# MJ818_clone_-_all_driver.net
KiCad netlist of a schematic drawn in EAGLE
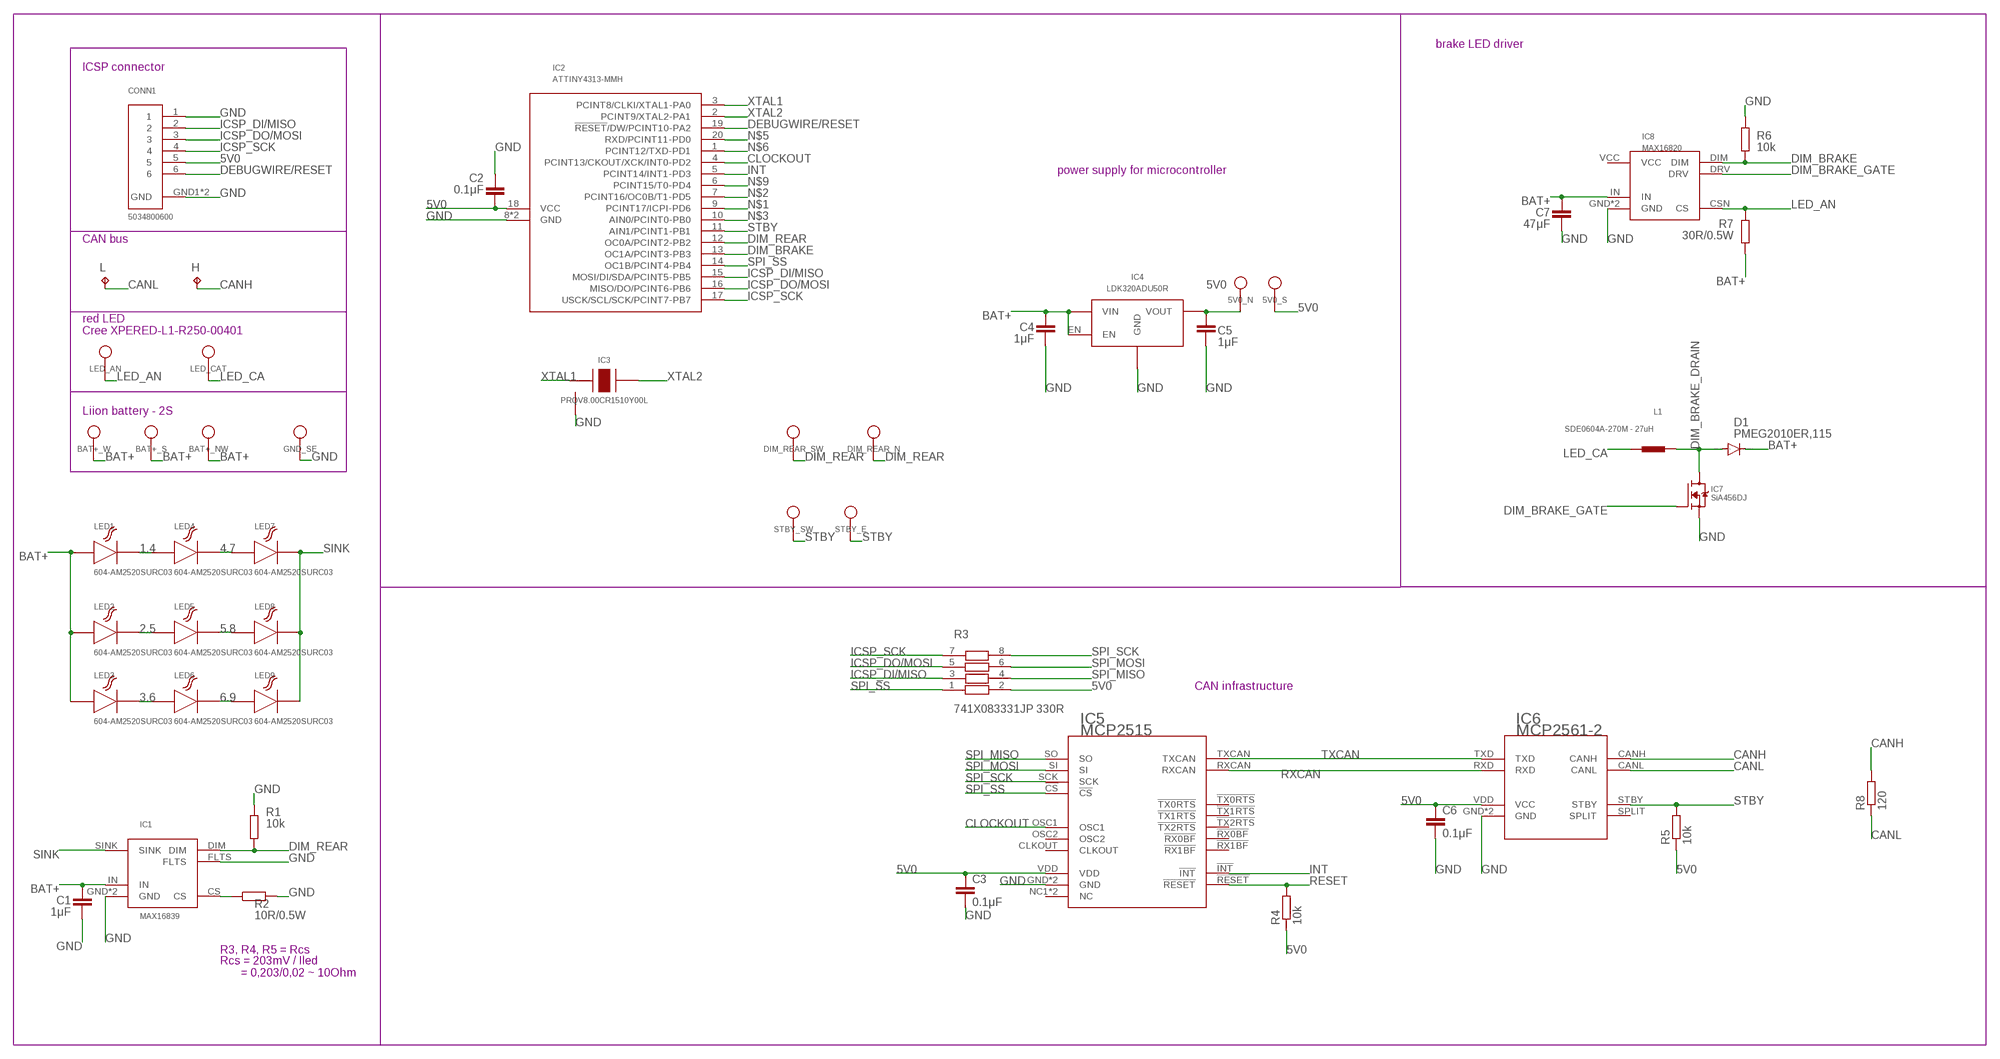
[diagram p0: schematic, sheet 1]

(export (version "E")
  (design (tool "Eeschema 10.0.6"))
  (components
    (comp (ref "5V0_N")
      (value "TPTH")
      (footprint "eagle-import:TH")
      (libsource (lib "eagle-import") (part "TPTH"))
    )
    (comp (ref "5V0_S")
      (value "TPTH")
      (footprint "eagle-import:TH")
      (libsource (lib "eagle-import") (part "TPTH"))
    )
    (comp (ref "BAT+_NW")
      (value "TPTH")
      (footprint "eagle-import:TH")
      (libsource (lib "eagle-import") (part "TPTH"))
    )
    (comp (ref "BAT+_S")
      (value "TPSMT")
      (footprint "eagle-import:SMT")
      (libsource (lib "eagle-import") (part "TPSMT"))
    )
    (comp (ref "BAT+_W")
      (value "TPTH")
      (footprint "eagle-import:TH")
      (libsource (lib "eagle-import") (part "TPTH"))
    )
    (comp (ref "C1")
      (value "1μF")
      (footprint "eagle-import:C0402")
      (libsource (lib "eagle-import") (part "C-EUC0402"))
    )
    (comp (ref "C2")
      (value "0.1μF")
      (footprint "eagle-import:C0402")
      (libsource (lib "eagle-import") (part "C-EUC0402"))
    )
    (comp (ref "C3")
      (value "0.1μF")
      (footprint "eagle-import:C1206")
      (libsource (lib "eagle-import") (part "C-EUC1206"))
    )
    (comp (ref "C4")
      (value "1μF")
      (footprint "eagle-import:C0402")
      (libsource (lib "eagle-import") (part "C-EUC0402"))
    )
    (comp (ref "C5")
      (value "1μF")
      (footprint "eagle-import:C0402")
      (libsource (lib "eagle-import") (part "C-EUC0402"))
    )
    (comp (ref "C6")
      (value "0.1μF")
      (footprint "eagle-import:C1206")
      (libsource (lib "eagle-import") (part "C-EUC1206"))
    )
    (comp (ref "C7")
      (value "47μF")
      (footprint "eagle-import:C1206")
      (libsource (lib "eagle-import") (part "C-EUC1206"))
    )
    (comp (ref "CONN1")
      (value "5034800600")
      (footprint "eagle-import:SMT")
      (libsource (lib "eagle-import") (part "5034800600"))
    )
    (comp (ref "D1")
      (value "PMEG2010ER,115")
      (footprint "eagle-import:SOD123")
      (libsource (lib "eagle-import") (part "DIODE-SOD123"))
    )
    (comp (ref "DIM_REAR_N")
      (value "TPTH")
      (footprint "eagle-import:TH")
      (libsource (lib "eagle-import") (part "TPTH"))
    )
    (comp (ref "DIM_REAR_SW")
      (value "TPTH")
      (footprint "eagle-import:TH")
      (libsource (lib "eagle-import") (part "TPTH"))
    )
    (comp (ref "GND_SE")
      (value "TPTH")
      (footprint "eagle-import:TH")
      (libsource (lib "eagle-import") (part "TPTH"))
    )
    (comp (ref "H")
      (value "TPB2,54")
      (footprint "eagle-import:B2,54")
      (libsource (lib "eagle-import") (part "TPB2,54"))
    )
    (comp (ref "IC1")
      (value "MAX16839")
      (footprint "eagle-import:TDFN-6-EP")
      (libsource (lib "eagle-import") (part "MAX16839"))
    )
    (comp (ref "IC2")
      (value "ATTINY4313-MMH")
      (footprint "eagle-import:VQFN-20")
      (fields (field (name "SPICEPREFIX") "X"))
      (libsource (lib "eagle-import") (part "ATTINY4313VQFN-20"))
    )
    (comp (ref "IC3")
      (value "PRQV8.00CR1510Y00L")
      (footprint "eagle-import:SMT")
      (libsource (lib "eagle-import") (part "PRQV"))
    )
    (comp (ref "IC4")
      (value "LDK320ADU50R")
      (footprint "eagle-import:SOT-23-5L")
      (libsource (lib "eagle-import") (part "LDK320SOT-23-5L"))
    )
    (comp (ref "IC5")
      (value "MCP2515")
      (footprint "eagle-import:QFN20")
      (libsource (lib "eagle-import") (part "MCP2515-I-ML"))
    )
    (comp (ref "IC6")
      (value "MCP2561-2")
      (footprint "eagle-import:DFN10")
      (libsource (lib "eagle-import") (part "MCP2561-2"))
    )
    (comp (ref "IC7")
      (value "SiA456DJ")
      (footprint "eagle-import:SC-70-6")
      (libsource (lib "eagle-import") (part "SIA456DJ"))
    )
    (comp (ref "IC8")
      (value "MAX16820")
      (footprint "eagle-import:TDFN-6-EP")
      (libsource (lib "eagle-import") (part "MAX16820"))
    )
    (comp (ref "L")
      (value "TPB2,54")
      (footprint "eagle-import:B2,54")
      (libsource (lib "eagle-import") (part "TPB2,54"))
    )
    (comp (ref "L1")
      (value "SDE0604A-270M - 27uH")
      (footprint "eagle-import:SMT")
      (libsource (lib "eagle-import") (part "DE0604A-778075"))
    )
    (comp (ref "LED1")
      (value "604-AM2520SURC03")
      (footprint "eagle-import:SMD")
      (libsource (lib "eagle-import") (part "AM2520SURC03-31454"))
    )
    (comp (ref "LED2")
      (value "604-AM2520SURC03")
      (footprint "eagle-import:SMD")
      (libsource (lib "eagle-import") (part "AM2520SURC03-31454"))
    )
    (comp (ref "LED3")
      (value "604-AM2520SURC03")
      (footprint "eagle-import:SMD")
      (libsource (lib "eagle-import") (part "AM2520SURC03-31454"))
    )
    (comp (ref "LED4")
      (value "604-AM2520SURC03")
      (footprint "eagle-import:SMD")
      (libsource (lib "eagle-import") (part "AM2520SURC03-31454"))
    )
    (comp (ref "LED5")
      (value "604-AM2520SURC03")
      (footprint "eagle-import:SMD")
      (libsource (lib "eagle-import") (part "AM2520SURC03-31454"))
    )
    (comp (ref "LED6")
      (value "604-AM2520SURC03")
      (footprint "eagle-import:SMD")
      (libsource (lib "eagle-import") (part "AM2520SURC03-31454"))
    )
    (comp (ref "LED7")
      (value "604-AM2520SURC03")
      (footprint "eagle-import:SMD")
      (libsource (lib "eagle-import") (part "AM2520SURC03-31454"))
    )
    (comp (ref "LED8")
      (value "604-AM2520SURC03")
      (footprint "eagle-import:SMD")
      (libsource (lib "eagle-import") (part "AM2520SURC03-31454"))
    )
    (comp (ref "LED9")
      (value "604-AM2520SURC03")
      (footprint "eagle-import:SMD")
      (libsource (lib "eagle-import") (part "AM2520SURC03-31454"))
    )
    (comp (ref "LED_AN")
      (value "TPTH")
      (footprint "eagle-import:TH")
      (libsource (lib "eagle-import") (part "TPTH"))
    )
    (comp (ref "LED_CAT")
      (value "TPTH")
      (footprint "eagle-import:TH")
      (libsource (lib "eagle-import") (part "TPTH"))
    )
    (comp (ref "R1")
      (value "10k")
      (footprint "eagle-import:R0402")
      (libsource (lib "eagle-import") (part "R-EU_R0402"))
    )
    (comp (ref "R2")
      (value "10R/0.5W")
      (footprint "eagle-import:R0603")
      (libsource (lib "eagle-import") (part "R-EU_R0603"))
    )
    (comp (ref "R3")
      (value "741X083331JP 330R")
      (footprint "eagle-import:0402")
      (libsource (lib "eagle-import") (part "741X083331JP"))
    )
    (comp (ref "R4")
      (value "10k")
      (footprint "eagle-import:R0402")
      (libsource (lib "eagle-import") (part "R-EU_R0402"))
    )
    (comp (ref "R5")
      (value "10k")
      (footprint "eagle-import:R0603")
      (libsource (lib "eagle-import") (part "R-EU_R0603"))
    )
    (comp (ref "R6")
      (value "10k")
      (footprint "eagle-import:R0402")
      (libsource (lib "eagle-import") (part "R-EU_R0402"))
    )
    (comp (ref "R7")
      (value "30R/0.5W")
      (footprint "eagle-import:R1206")
      (libsource (lib "eagle-import") (part "R-EU_R1206"))
    )
    (comp (ref "R8")
      (value "120")
      (footprint "eagle-import:R0805")
      (libsource (lib "eagle-import") (part "R-EU_R0805"))
    )
    (comp (ref "STBY_E")
      (value "TPTH")
      (footprint "eagle-import:TH")
      (libsource (lib "eagle-import") (part "TPTH"))
    )
    (comp (ref "STBY_SW")
      (value "TPTH")
      (footprint "eagle-import:TH")
      (libsource (lib "eagle-import") (part "TPTH"))
    )
  )
  (nets
    (net (code "1") (name "/1.4") (class "Default")
      (node (ref "LED1") (pin "C") (pinfunction "C_C") (pintype "bidirectional"))
      (node (ref "LED4") (pin "A") (pinfunction "A_A") (pintype "bidirectional"))
    )
    (net (code "2") (name "/2.5") (class "Default")
      (node (ref "LED2") (pin "C") (pinfunction "C_C") (pintype "bidirectional"))
      (node (ref "LED5") (pin "A") (pinfunction "A_A") (pintype "bidirectional"))
    )
    (net (code "3") (name "/3.6") (class "Default")
      (node (ref "LED3") (pin "C") (pinfunction "C_C") (pintype "bidirectional"))
      (node (ref "LED6") (pin "A") (pinfunction "A_A") (pintype "bidirectional"))
    )
    (net (code "4") (name "/4.7") (class "Default")
      (node (ref "LED4") (pin "C") (pinfunction "C_C") (pintype "bidirectional"))
      (node (ref "LED7") (pin "A") (pinfunction "A_A") (pintype "bidirectional"))
    )
    (net (code "5") (name "/5.8") (class "Default")
      (node (ref "LED5") (pin "C") (pinfunction "C_C") (pintype "bidirectional"))
      (node (ref "LED8") (pin "A") (pinfunction "A_A") (pintype "bidirectional"))
    )
    (net (code "6") (name "/5V0") (class "Default")
      (node (ref "5V0_N") (pin "TP$1") (pinfunction "TP$1_TP$1") (pintype "bidirectional"))
      (node (ref "5V0_S") (pin "TP$1") (pinfunction "TP$1_TP$1") (pintype "bidirectional"))
      (node (ref "C2") (pin "1") (pinfunction "1_1") (pintype "passive"))
      (node (ref "C3") (pin "1") (pinfunction "1_1") (pintype "passive"))
      (node (ref "C5") (pin "2") (pinfunction "2_2") (pintype "passive"))
      (node (ref "C6") (pin "1") (pinfunction "1_1") (pintype "passive"))
      (node (ref "CONN1") (pin "5") (pinfunction "5_5") (pintype "bidirectional"))
      (node (ref "IC2") (pin "18") (pinfunction "VCC_18") (pintype "bidirectional"))
      (node (ref "IC4") (pin "OUT") (pinfunction "VOUT_OUT") (pintype "bidirectional"))
      (node (ref "IC5") (pin "VDD") (pinfunction "VDD_VDD") (pintype "power_in"))
      (node (ref "IC6") (pin "VDD") (pinfunction "VCC_VDD") (pintype "power_in"))
      (node (ref "R3") (pin "2") (pinfunction "2_2") (pintype "bidirectional"))
      (node (ref "R4") (pin "1") (pinfunction "1_1") (pintype "passive"))
      (node (ref "R5") (pin "1") (pinfunction "1_1") (pintype "passive"))
    )
    (net (code "7") (name "/6.9") (class "Default")
      (node (ref "LED6") (pin "C") (pinfunction "C_C") (pintype "bidirectional"))
      (node (ref "LED9") (pin "A") (pinfunction "A_A") (pintype "bidirectional"))
    )
    (net (code "8") (name "/BAT+") (class "Default")
      (node (ref "BAT+_NW") (pin "TP$1") (pinfunction "TP$1_TP$1") (pintype "bidirectional"))
      (node (ref "BAT+_S") (pin "P$1") (pinfunction "TP$1_P$1") (pintype "bidirectional"))
      (node (ref "BAT+_W") (pin "TP$1") (pinfunction "TP$1_TP$1") (pintype "bidirectional"))
      (node (ref "C1") (pin "2") (pinfunction "2_2") (pintype "passive"))
      (node (ref "C4") (pin "1") (pinfunction "1_1") (pintype "passive"))
      (node (ref "C7") (pin "1") (pinfunction "1_1") (pintype "passive"))
      (node (ref "D1") (pin "C") (pinfunction "C_C") (pintype "passive"))
      (node (ref "IC1") (pin "IN") (pinfunction "IN_IN") (pintype "power_in"))
      (node (ref "IC4") (pin "EN") (pinfunction "EN_EN") (pintype "bidirectional"))
      (node (ref "IC4") (pin "IN") (pinfunction "VIN_IN") (pintype "bidirectional"))
      (node (ref "IC8") (pin "IN") (pinfunction "IN_IN") (pintype "power_in"))
      (node (ref "LED1") (pin "A") (pinfunction "A_A") (pintype "bidirectional"))
      (node (ref "LED2") (pin "A") (pinfunction "A_A") (pintype "bidirectional"))
      (node (ref "LED3") (pin "A") (pinfunction "A_A") (pintype "bidirectional"))
      (node (ref "R7") (pin "2") (pinfunction "2_2") (pintype "passive"))
    )
    (net (code "9") (name "/CANH") (class "Default")
      (node (ref "H") (pin "TP") (pinfunction "TP_TP") (pintype "input"))
      (node (ref "IC6") (pin "CANH") (pinfunction "CANH_CANH") (pintype "bidirectional"))
      (node (ref "R8") (pin "2") (pinfunction "2_2") (pintype "passive"))
    )
    (net (code "10") (name "/CANL") (class "Default")
      (node (ref "IC6") (pin "CANL") (pinfunction "CANL_CANL") (pintype "bidirectional"))
      (node (ref "L") (pin "TP") (pinfunction "TP_TP") (pintype "input"))
      (node (ref "R8") (pin "1") (pinfunction "1_1") (pintype "passive"))
    )
    (net (code "11") (name "/CLOCKOUT") (class "Default")
      (node (ref "IC2") (pin "4") (pinfunction "PCINT13/CKOUT/XCK/INT0-PD2_4") (pintype "bidirectional"))
      (node (ref "IC5") (pin "OSC1") (pinfunction "OSC1_OSC1") (pintype "bidirectional"))
    )
    (net (code "12") (name "/DEBUGWIRE{slash}RESET") (class "Default")
      (node (ref "CONN1") (pin "6") (pinfunction "6_6") (pintype "bidirectional"))
      (node (ref "IC2") (pin "19") (pinfunction "~{RESET}/DW/PCINT10-PA2_19") (pintype "bidirectional"))
    )
    (net (code "13") (name "/DIM_BRAKE") (class "Default")
      (node (ref "IC2") (pin "13") (pinfunction "OC1A/PCINT3-PB3_13") (pintype "bidirectional"))
      (node (ref "IC8") (pin "DIM") (pinfunction "DIM_DIM") (pintype "bidirectional"))
      (node (ref "R6") (pin "1") (pinfunction "1_1") (pintype "passive"))
    )
    (net (code "14") (name "/DIM_BRAKE_DRAIN") (class "Default")
      (node (ref "D1") (pin "A") (pinfunction "A_A") (pintype "passive"))
      (node (ref "IC7") (pin "1D") (pinfunction "D_1D") (pintype "passive"))
      (node (ref "IC7") (pin "2D") (pinfunction "D_2D") (pintype "passive"))
      (node (ref "IC7") (pin "5D") (pinfunction "D_5D") (pintype "passive"))
      (node (ref "IC7") (pin "6D") (pinfunction "D_6D") (pintype "passive"))
      (node (ref "IC7") (pin "D") (pinfunction "D_D") (pintype "passive"))
      (node (ref "L1") (pin "P$2") (pinfunction "P$2_P$2") (pintype "bidirectional"))
    )
    (net (code "15") (name "/DIM_BRAKE_GATE") (class "Default")
      (node (ref "IC7") (pin "3G") (pinfunction "G_3G") (pintype "passive"))
      (node (ref "IC8") (pin "DRV") (pinfunction "DRV_DRV") (pintype "bidirectional"))
    )
    (net (code "16") (name "/DIM_REAR") (class "Default")
      (node (ref "DIM_REAR_N") (pin "TP$1") (pinfunction "TP$1_TP$1") (pintype "bidirectional"))
      (node (ref "DIM_REAR_SW") (pin "TP$1") (pinfunction "TP$1_TP$1") (pintype "bidirectional"))
      (node (ref "IC1") (pin "DIM") (pinfunction "DIM_DIM") (pintype "bidirectional"))
      (node (ref "IC2") (pin "12") (pinfunction "OC0A/PCINT2-PB2_12") (pintype "bidirectional"))
      (node (ref "R1") (pin "1") (pinfunction "1_1") (pintype "passive"))
    )
    (net (code "17") (name "/GND") (class "Default")
      (node (ref "C1") (pin "1") (pinfunction "1_1") (pintype "passive"))
      (node (ref "C2") (pin "2") (pinfunction "2_2") (pintype "passive"))
      (node (ref "C3") (pin "2") (pinfunction "2_2") (pintype "passive"))
      (node (ref "C4") (pin "2") (pinfunction "2_2") (pintype "passive"))
      (node (ref "C5") (pin "1") (pinfunction "1_1") (pintype "passive"))
      (node (ref "C6") (pin "2") (pinfunction "2_2") (pintype "passive"))
      (node (ref "C7") (pin "2") (pinfunction "2_2") (pintype "passive"))
      (node (ref "CONN1") (pin "1") (pinfunction "1_1") (pintype "bidirectional"))
      (node (ref "CONN1") (pin "GND1") (pinfunction "GND_GND1") (pintype "bidirectional"))
      (node (ref "CONN1") (pin "GND2") (pinfunction "GND_GND2") (pintype "bidirectional"))
      (node (ref "GND_SE") (pin "TP$1") (pinfunction "TP$1_TP$1") (pintype "bidirectional"))
      (node (ref "IC1") (pin "FLTS") (pinfunction "FLTS_FLTS") (pintype "bidirectional"))
      (node (ref "IC1") (pin "GND") (pinfunction "GND_GND") (pintype "power_in"))
      (node (ref "IC1") (pin "GND1") (pinfunction "GND_GND1") (pintype "power_in"))
      (node (ref "IC2") (pin "8") (pinfunction "GND_8") (pintype "bidirectional"))
      (node (ref "IC2") (pin "GND") (pinfunction "GND_GND") (pintype "bidirectional"))
      (node (ref "IC3") (pin "GND") (pinfunction "GND_GND") (pintype "bidirectional"))
      (node (ref "IC4") (pin "GND") (pinfunction "GND_GND") (pintype "bidirectional"))
      (node (ref "IC5") (pin "GND") (pinfunction "GND_GND") (pintype "power_in"))
      (node (ref "IC5") (pin "GND6") (pinfunction "GND_GND6") (pintype "power_in"))
      (node (ref "IC6") (pin "GND") (pinfunction "GND_GND") (pintype "power_in"))
      (node (ref "IC6") (pin "VSS") (pinfunction "GND_VSS") (pintype "power_in"))
      (node (ref "IC7") (pin "4S") (pinfunction "S_4S") (pintype "passive"))
      (node (ref "IC7") (pin "S") (pinfunction "S_S") (pintype "passive"))
      (node (ref "IC8") (pin "GND") (pinfunction "GND_GND") (pintype "power_in"))
      (node (ref "IC8") (pin "GND1") (pinfunction "GND_GND1") (pintype "power_in"))
      (node (ref "R1") (pin "2") (pinfunction "2_2") (pintype "passive"))
      (node (ref "R2") (pin "2") (pinfunction "2_2") (pintype "passive"))
      (node (ref "R6") (pin "2") (pinfunction "2_2") (pintype "passive"))
    )
    (net (code "18") (name "/ICSP_DI{slash}MISO") (class "Default")
      (node (ref "CONN1") (pin "2") (pinfunction "2_2") (pintype "bidirectional"))
      (node (ref "IC2") (pin "15") (pinfunction "MOSI/DI/SDA/PCINT5-PB5_15") (pintype "bidirectional"))
      (node (ref "R3") (pin "3") (pinfunction "3_3") (pintype "bidirectional"))
    )
    (net (code "19") (name "/ICSP_DO{slash}MOSI") (class "Default")
      (node (ref "CONN1") (pin "3") (pinfunction "3_3") (pintype "bidirectional"))
      (node (ref "IC2") (pin "16") (pinfunction "MISO/DO/PCINT6-PB6_16") (pintype "bidirectional"))
      (node (ref "R3") (pin "5") (pinfunction "5_5") (pintype "bidirectional"))
    )
    (net (code "20") (name "/ICSP_SCK") (class "Default")
      (node (ref "CONN1") (pin "4") (pinfunction "4_4") (pintype "bidirectional"))
      (node (ref "IC2") (pin "17") (pinfunction "USCK/SCL/SCK/PCINT7-PB7_17") (pintype "bidirectional"))
      (node (ref "R3") (pin "7") (pinfunction "7_7") (pintype "bidirectional"))
    )
    (net (code "21") (name "/INT") (class "Default")
      (node (ref "IC2") (pin "5") (pinfunction "PCINT14/INT1-PD3_5") (pintype "bidirectional"))
      (node (ref "IC5") (pin "!INT!") (pinfunction "~{INT}_!INT!") (pintype "bidirectional"))
    )
    (net (code "22") (name "/LED_AN") (class "Default")
      (node (ref "IC8") (pin "CSN") (pinfunction "CS_CSN") (pintype "bidirectional"))
      (node (ref "LED_AN") (pin "TP$1") (pinfunction "TP$1_TP$1") (pintype "bidirectional"))
      (node (ref "R7") (pin "1") (pinfunction "1_1") (pintype "passive"))
    )
    (net (code "23") (name "/LED_CA") (class "Default")
      (node (ref "L1") (pin "P$1") (pinfunction "P$1_P$1") (pintype "bidirectional"))
      (node (ref "LED_CAT") (pin "TP$1") (pinfunction "TP$1_TP$1") (pintype "bidirectional"))
    )
    (net (code "24") (name "/N$1") (class "Default")
      (node (ref "IC2") (pin "9") (pinfunction "PCINT17/ICPI-PD6_9") (pintype "bidirectional"))
    )
    (net (code "25") (name "/N$2") (class "Default")
      (node (ref "IC2") (pin "7") (pinfunction "PCINT16/OC0B/T1-PD5_7") (pintype "bidirectional"))
    )
    (net (code "26") (name "/N$3") (class "Default")
      (node (ref "IC2") (pin "10") (pinfunction "AIN0/PCINT0-PB0_10") (pintype "bidirectional"))
    )
    (net (code "27") (name "/N$5") (class "Default")
      (node (ref "IC2") (pin "20") (pinfunction "RXD/PCINT11-PD0_20") (pintype "bidirectional"))
    )
    (net (code "28") (name "/N$6") (class "Default")
      (node (ref "IC2") (pin "1") (pinfunction "PCINT12/TXD-PD1_1") (pintype "bidirectional"))
    )
    (net (code "29") (name "/N$9") (class "Default")
      (node (ref "IC2") (pin "6") (pinfunction "PCINT15/T0-PD4_6") (pintype "bidirectional"))
    )
    (net (code "30") (name "/RESET") (class "Default")
      (node (ref "IC5") (pin "!RESET!") (pinfunction "~{RESET}_!RESET!") (pintype "bidirectional"))
      (node (ref "R4") (pin "2") (pinfunction "2_2") (pintype "passive"))
    )
    (net (code "31") (name "/RXCAN") (class "Default")
      (node (ref "IC5") (pin "RXCAN") (pinfunction "RXCAN_RXCAN") (pintype "input"))
      (node (ref "IC6") (pin "RXD") (pinfunction "RXD_RXD") (pintype "output"))
    )
    (net (code "32") (name "/SINK") (class "Default")
      (node (ref "IC1") (pin "SINK") (pinfunction "SINK_SINK") (pintype "power_in"))
      (node (ref "LED7") (pin "C") (pinfunction "C_C") (pintype "bidirectional"))
      (node (ref "LED8") (pin "C") (pinfunction "C_C") (pintype "bidirectional"))
      (node (ref "LED9") (pin "C") (pinfunction "C_C") (pintype "bidirectional"))
    )
    (net (code "33") (name "/SPI_MISO") (class "Default")
      (node (ref "IC5") (pin "SO") (pinfunction "SO_SO") (pintype "output"))
      (node (ref "R3") (pin "4") (pinfunction "4_4") (pintype "bidirectional"))
    )
    (net (code "34") (name "/SPI_MOSI") (class "Default")
      (node (ref "IC5") (pin "SI") (pinfunction "SI_SI") (pintype "input"))
      (node (ref "R3") (pin "6") (pinfunction "6_6") (pintype "bidirectional"))
    )
    (net (code "35") (name "/SPI_SCK") (class "Default")
      (node (ref "IC5") (pin "SCK") (pinfunction "SCK_SCK") (pintype "bidirectional"))
      (node (ref "R3") (pin "8") (pinfunction "8_8") (pintype "bidirectional"))
    )
    (net (code "36") (name "/SPI_SS") (class "Default")
      (node (ref "IC2") (pin "14") (pinfunction "OC1B/PCINT4-PB4_14") (pintype "bidirectional"))
      (node (ref "IC5") (pin "!CS!") (pinfunction "~{CS}_!CS!") (pintype "bidirectional"))
      (node (ref "R3") (pin "1") (pinfunction "1_1") (pintype "bidirectional"))
    )
    (net (code "37") (name "/STBY") (class "Default")
      (node (ref "IC2") (pin "11") (pinfunction "AIN1/PCINT1-PB1_11") (pintype "bidirectional"))
      (node (ref "IC6") (pin "STBY") (pinfunction "STBY_STBY") (pintype "bidirectional"))
      (node (ref "R5") (pin "2") (pinfunction "2_2") (pintype "passive"))
      (node (ref "STBY_E") (pin "TP$1") (pinfunction "TP$1_TP$1") (pintype "bidirectional"))
      (node (ref "STBY_SW") (pin "TP$1") (pinfunction "TP$1_TP$1") (pintype "bidirectional"))
    )
    (net (code "38") (name "/TXCAN") (class "Default")
      (node (ref "IC5") (pin "TXCAN") (pinfunction "TXCAN_TXCAN") (pintype "output"))
      (node (ref "IC6") (pin "TXD") (pinfunction "TXD_TXD") (pintype "input"))
    )
    (net (code "39") (name "/VCC") (class "Default")
      (node (ref "IC8") (pin "VCC") (pinfunction "VCC_VCC") (pintype "power_in"))
    )
    (net (code "40") (name "/XTAL1") (class "Default")
      (node (ref "IC2") (pin "3") (pinfunction "PCINT8/CLKI/XTAL1-PA0_3") (pintype "bidirectional"))
      (node (ref "IC3") (pin "XTAL1") (pinfunction "XTAL1_XTAL1") (pintype "bidirectional"))
    )
    (net (code "41") (name "/XTAL2") (class "Default")
      (node (ref "IC2") (pin "2") (pinfunction "PCINT9/XTAL2-PA1_2") (pintype "bidirectional"))
      (node (ref "IC3") (pin "XTAL2") (pinfunction "XTAL2_XTAL2") (pintype "bidirectional"))
    )
    (net (code "42") (name "Net-(IC1-PadCS)") (class "Default")
      (node (ref "IC1") (pin "CS") (pinfunction "CS_CS") (pintype "bidirectional"))
      (node (ref "R2") (pin "1") (pinfunction "1_1") (pintype "passive"))
    )
    (net (code "43") (name "unconnected-(IC5-NC-PadNC1)") (class "Default")
      (node (ref "IC5") (pin "NC1") (pinfunction "NC_NC1") (pintype "no_connect"))
    )
    (net (code "44") (name "unconnected-(IC5-NC-PadNC2)") (class "Default")
      (node (ref "IC5") (pin "NC2") (pinfunction "NC_NC2") (pintype "no_connect"))
    )
    (net (code "45") (name "unconnected-(IC5-PadCLKOUT)") (class "Default")
      (node (ref "IC5") (pin "CLKOUT") (pinfunction "CLKOUT_CLKOUT") (pintype "bidirectional"))
    )
    (net (code "46") (name "unconnected-(IC5-PadOSC2)") (class "Default")
      (node (ref "IC5") (pin "OSC2") (pinfunction "OSC2_OSC2") (pintype "bidirectional"))
    )
    (net (code "47") (name "unconnected-(IC5-~{RX0BF}-Pad!RX0BF!)") (class "Default")
      (node (ref "IC5") (pin "!RX0BF!") (pinfunction "~{RX0BF}_!RX0BF!") (pintype "bidirectional"))
    )
    (net (code "48") (name "unconnected-(IC5-~{RX1BF}-Pad!RX1BF!)") (class "Default")
      (node (ref "IC5") (pin "!RX1BF!") (pinfunction "~{RX1BF}_!RX1BF!") (pintype "bidirectional"))
    )
    (net (code "49") (name "unconnected-(IC5-~{TX0RTS}-Pad!TX0RTS!)") (class "Default")
      (node (ref "IC5") (pin "!TX0RTS!") (pinfunction "~{TX0RTS}_!TX0RTS!") (pintype "bidirectional"))
    )
    (net (code "50") (name "unconnected-(IC5-~{TX1RTS}-Pad!TX1RTS!)") (class "Default")
      (node (ref "IC5") (pin "!TX1RTS!") (pinfunction "~{TX1RTS}_!TX1RTS!") (pintype "bidirectional"))
    )
    (net (code "51") (name "unconnected-(IC5-~{TX2RTS}-Pad!TX2RTS!)") (class "Default")
      (node (ref "IC5") (pin "!TX2RTS!") (pinfunction "~{TX2RTS}_!TX2RTS!") (pintype "bidirectional"))
    )
    (net (code "52") (name "unconnected-(IC6-PadSPLIT)") (class "Default")
      (node (ref "IC6") (pin "SPLIT") (pinfunction "SPLIT_SPLIT") (pintype "bidirectional"))
    )
  )
)
